# k1fm-pico-balloon-v1_1.net
KiCad netlist of a schematic drawn in EAGLE
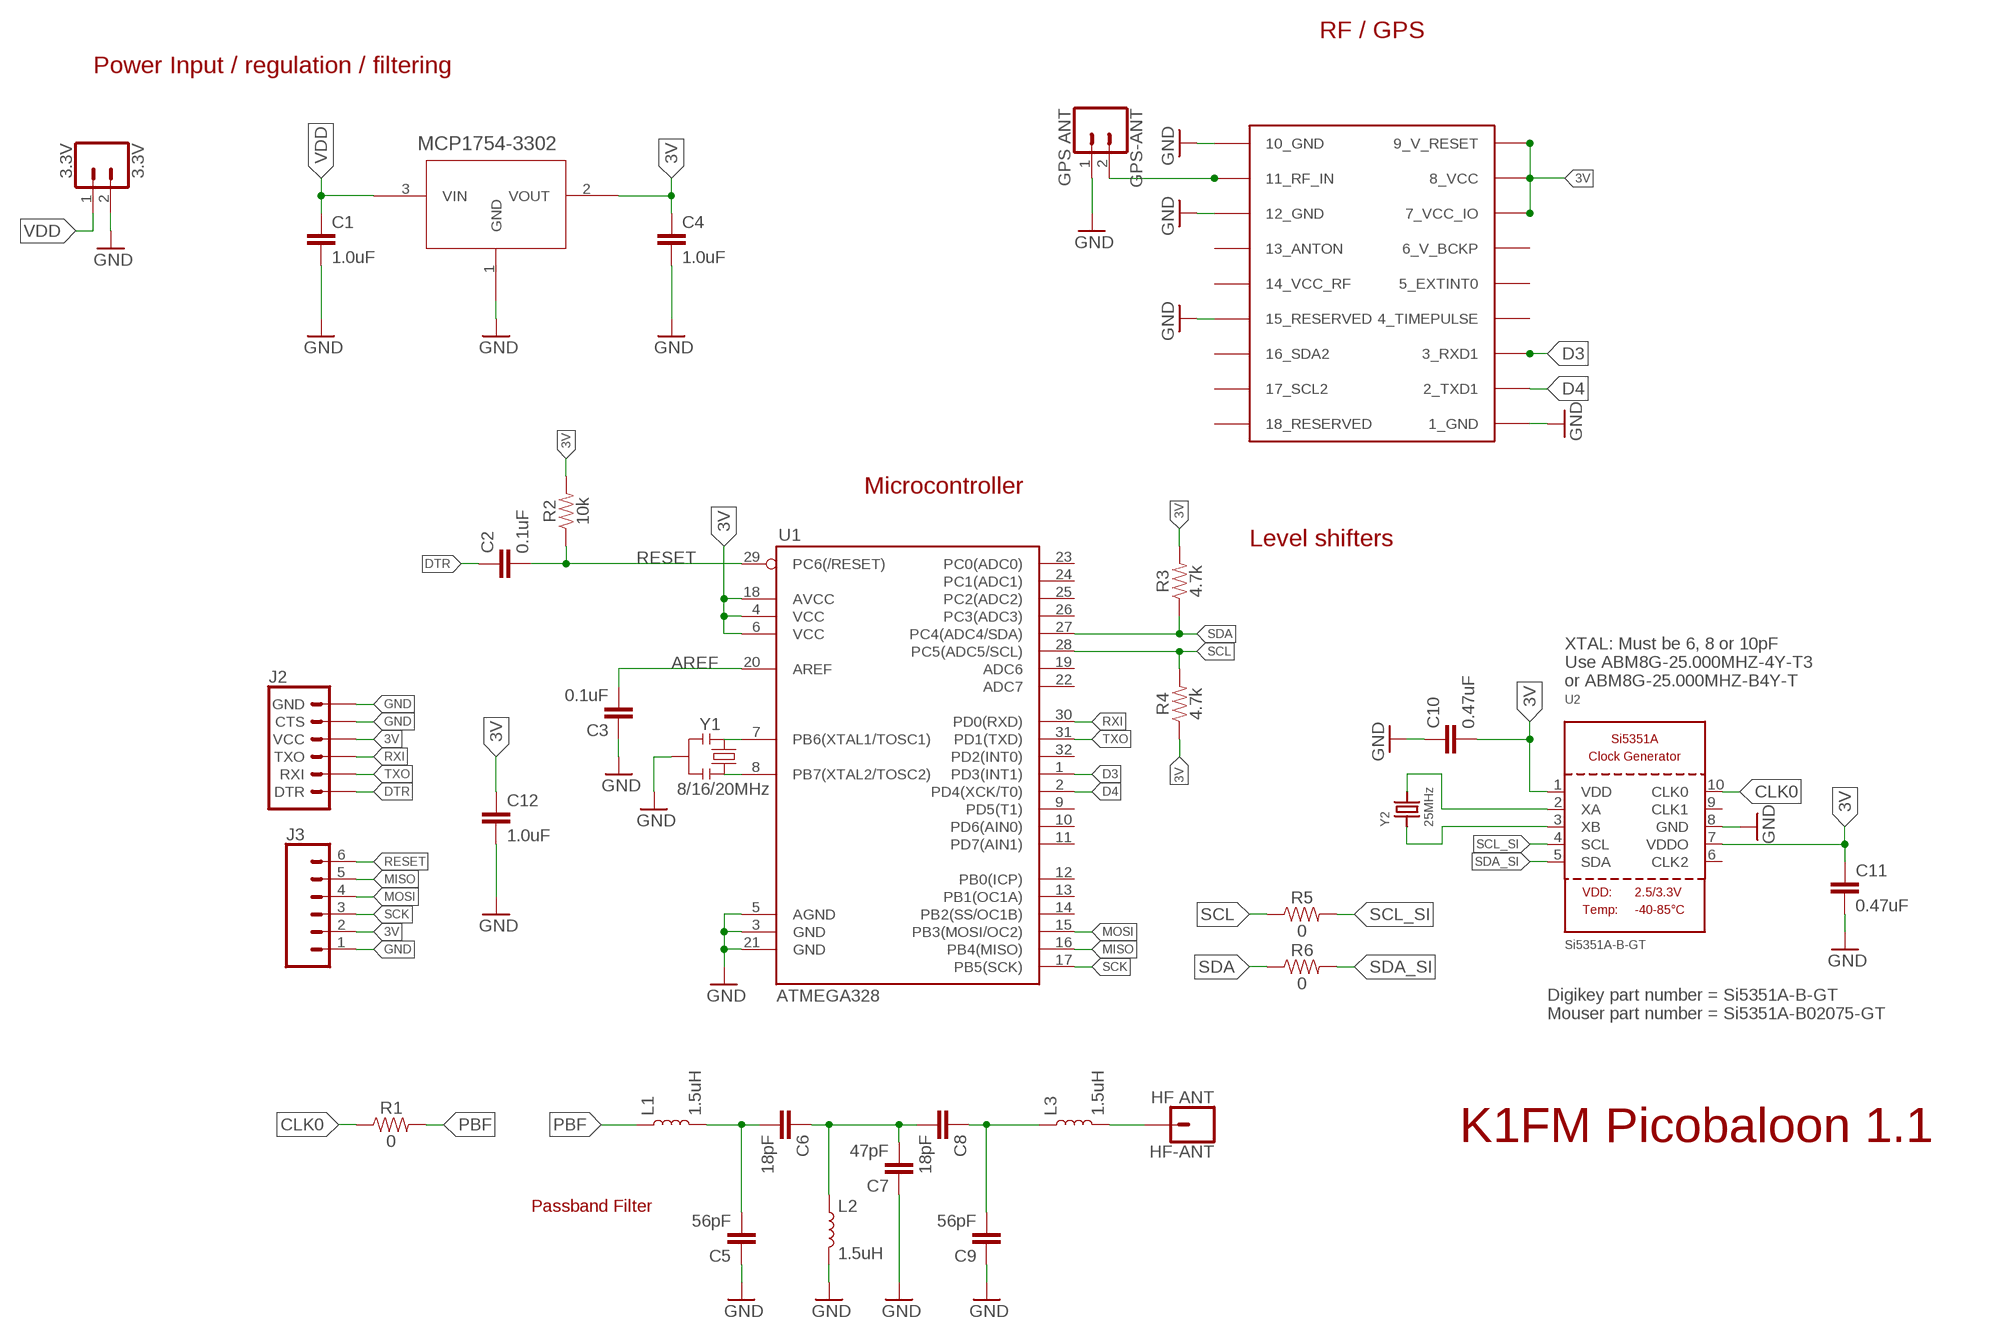
[diagram p0: schematic, sheet 1]

(export (version "E")
  (design (tool "Eeschema 10.0.6"))
  (components
    (comp (ref "3.3V")
      (value "3.3V")
      (footprint "eagle-import:1X02")
      (libsource (lib "eagle-import") (part "CONN_02"))
    )
    (comp (ref "C1")
      (value "1.0uF")
      (footprint "eagle-import:0603")
      (libsource (lib "eagle-import") (part "1.0UF-0603-16V-10%"))
    )
    (comp (ref "C2")
      (value "0.1uF")
      (footprint "eagle-import:0603")
      (libsource (lib "eagle-import") (part "0.1UF-0603-25V-5%"))
    )
    (comp (ref "C3")
      (value "0.1uF")
      (footprint "eagle-import:0603")
      (libsource (lib "eagle-import") (part "0.1UF-0603-25V-5%"))
    )
    (comp (ref "C4")
      (value "1.0uF")
      (footprint "eagle-import:0603")
      (libsource (lib "eagle-import") (part "1.0UF-0603-16V-10%"))
    )
    (comp (ref "C5")
      (value "56pF")
      (footprint "eagle-import:0603")
      (libsource (lib "eagle-import") (part "0.1UF-0603-25V-5%"))
    )
    (comp (ref "C6")
      (value "18pF")
      (footprint "eagle-import:0603")
      (libsource (lib "eagle-import") (part "0.1UF-0603-25V-5%"))
    )
    (comp (ref "C7")
      (value "47pF")
      (footprint "eagle-import:0603")
      (libsource (lib "eagle-import") (part "0.1UF-0603-25V-5%"))
    )
    (comp (ref "C8")
      (value "18pF")
      (footprint "eagle-import:0603")
      (libsource (lib "eagle-import") (part "0.1UF-0603-25V-5%"))
    )
    (comp (ref "C9")
      (value "56pF")
      (footprint "eagle-import:0603")
      (libsource (lib "eagle-import") (part "0.1UF-0603-25V-5%"))
    )
    (comp (ref "C10")
      (value "0.47uF")
      (footprint "eagle-import:0603")
      (libsource (lib "eagle-import") (part "0.1UF-0603-25V-5%"))
    )
    (comp (ref "C11")
      (value "0.47uF")
      (footprint "eagle-import:0603")
      (libsource (lib "eagle-import") (part "0.1UF-0603-25V-5%"))
    )
    (comp (ref "C12")
      (value "1.0uF")
      (footprint "eagle-import:0603")
      (libsource (lib "eagle-import") (part "1.0UF-0603-16V-10%"))
    )
    (comp (ref "GPS-ANT")
      (value "GPS ANT")
      (footprint "eagle-import:1X02")
      (libsource (lib "eagle-import") (part "CONN_02"))
    )
    (comp (ref "GPS1")
      (value "UBLOX_MAX")
      (footprint "eagle-import:UBLOX_MAX")
      (libsource (lib "eagle-import") (part "UBLOX_MAX"))
    )
    (comp (ref "HF-ANT")
      (value "HF ANT")
      (footprint "eagle-import:1X01")
      (libsource (lib "eagle-import") (part "CONN_01"))
    )
    (comp (ref "J2")
      (value "6_PIN_SERIAL_TARGET")
      (footprint "eagle-import:1X06")
      (libsource (lib "eagle-import") (part "6_PIN_SERIAL_TARGET"))
    )
    (comp (ref "J3")
      (value "CONN_06SILK_FEMALE_PTH")
      (footprint "eagle-import:1X06")
      (libsource (lib "eagle-import") (part "CONN_06SILK_FEMALE_PTH"))
    )
    (comp (ref "L1")
      (value "1.5uH")
      (footprint "eagle-import:0603")
      (libsource (lib "eagle-import") (part "INDUCTOR-0603-33NH"))
    )
    (comp (ref "L2")
      (value "1.5uH")
      (footprint "eagle-import:0603")
      (libsource (lib "eagle-import") (part "INDUCTOR-0603-33NH"))
    )
    (comp (ref "L3")
      (value "1.5uH")
      (footprint "eagle-import:0603")
      (libsource (lib "eagle-import") (part "INDUCTOR-0603-33NH"))
    )
    (comp (ref "R1")
      (value "0")
      (footprint "eagle-import:0603")
      (libsource (lib "eagle-import") (part "0OHM-0603-1/10W-5%"))
    )
    (comp (ref "R2")
      (value "10k")
      (footprint "eagle-import:0603")
      (libsource (lib "eagle-import") (part "10KOHM-0603-1/10W-1%"))
    )
    (comp (ref "R3")
      (value "4.7k")
      (footprint "eagle-import:0603")
      (libsource (lib "eagle-import") (part "4.7KOHM-0603-1/10W-1%"))
    )
    (comp (ref "R4")
      (value "4.7k")
      (footprint "eagle-import:0603")
      (libsource (lib "eagle-import") (part "4.7KOHM-0603-1/10W-1%"))
    )
    (comp (ref "R5")
      (value "0")
      (footprint "eagle-import:0603")
      (libsource (lib "eagle-import") (part "0OHM-0603-1/10W-5%"))
    )
    (comp (ref "R6")
      (value "0")
      (footprint "eagle-import:0603")
      (libsource (lib "eagle-import") (part "0OHM-0603-1/10W-5%"))
    )
    (comp (ref "U1")
      (value "ATMEGA328")
      (footprint "eagle-import:TQFP32-08")
      (libsource (lib "eagle-import") (part "ATMEGA168"))
    )
    (comp (ref "U2")
      (value "Si5351A-B-GT")
      (footprint "eagle-import:MSOP10")
      (libsource (lib "eagle-import") (part "SI5351A"))
    )
    (comp (ref "U3")
      (value "MCP1754X-XXXXX/C")
      (footprint "eagle-import:SOT-23A_MC")
      (libsource (lib "eagle-import") (part "MCP1754X-XXXXX/C"))
    )
    (comp (ref "Y1")
      (value "8/16/20MHz")
      (footprint "eagle-import:RESONATOR-SMD-1_1")
      (libsource (lib "eagle-import") (part "RESONATOR1{colon}1"))
    )
    (comp (ref "Y2")
      (value "25MHz")
      (footprint "eagle-import:CRYSTAL_3.2X2.5")
      (libsource (lib "eagle-import") (part "CRYSTAL3.2X2.5"))
    )
  )
  (nets
    (net (code "1") (name "/AREF") (class "Default")
      (node (ref "C3") (pin "2") (pinfunction "2_2") (pintype "passive"))
      (node (ref "U1") (pin "20") (pinfunction "AREF_20") (pintype "bidirectional"))
    )
    (net (code "2") (name "3V") (class "Default")
      (node (ref "C10") (pin "2") (pinfunction "2_2") (pintype "passive"))
      (node (ref "C11") (pin "1") (pinfunction "1_1") (pintype "passive"))
      (node (ref "C12") (pin "1") (pinfunction "1_1") (pintype "passive"))
      (node (ref "C4") (pin "1") (pinfunction "1_1") (pintype "passive"))
      (node (ref "GPS1") (pin "7_VCC_IO") (pinfunction "7_VCC_IO_7_VCC_IO") (pintype "power_in"))
      (node (ref "GPS1") (pin "8_VCC") (pinfunction "8_VCC_8_VCC") (pintype "power_in"))
      (node (ref "GPS1") (pin "9_V_RESET") (pinfunction "9_V_RESET_9_V_RESET") (pintype "power_in"))
      (node (ref "J2") (pin "4") (pinfunction "VCC_4") (pintype "passive"))
      (node (ref "J3") (pin "2") (pinfunction "2_2") (pintype "passive"))
      (node (ref "R2") (pin "2") (pinfunction "2_2") (pintype "passive"))
      (node (ref "R3") (pin "2") (pinfunction "2_2") (pintype "passive"))
      (node (ref "R4") (pin "1") (pinfunction "1_1") (pintype "passive"))
      (node (ref "U1") (pin "18") (pinfunction "AVCC_18") (pintype "bidirectional"))
      (node (ref "U1") (pin "4") (pinfunction "VCC_4") (pintype "bidirectional"))
      (node (ref "U1") (pin "6") (pinfunction "VCC_6") (pintype "bidirectional"))
      (node (ref "U2") (pin "1") (pinfunction "VDD_1") (pintype "power_in"))
      (node (ref "U2") (pin "7") (pinfunction "VDDO_7") (pintype "power_in"))
      (node (ref "U3") (pin "2") (pinfunction "VOUT_2") (pintype "passive"))
    )
    (net (code "3") (name "CLK0") (class "Default")
      (node (ref "R1") (pin "1") (pinfunction "1_1") (pintype "passive"))
      (node (ref "U2") (pin "10") (pinfunction "CLK0_10") (pintype "output"))
    )
    (net (code "4") (name "D3") (class "Default")
      (node (ref "GPS1") (pin "3_RXD1") (pinfunction "3_RXD1_3_RXD1") (pintype "bidirectional"))
      (node (ref "U1") (pin "1") (pinfunction "PD3(INT1)_1") (pintype "bidirectional"))
    )
    (net (code "5") (name "D4") (class "Default")
      (node (ref "GPS1") (pin "2_TXD1") (pinfunction "2_TXD1_2_TXD1") (pintype "bidirectional"))
      (node (ref "U1") (pin "2") (pinfunction "PD4(XCK/T0)_2") (pintype "bidirectional"))
    )
    (net (code "6") (name "DTR") (class "Default")
      (node (ref "C2") (pin "1") (pinfunction "1_1") (pintype "passive"))
      (node (ref "J2") (pin "1") (pinfunction "DTR_1") (pintype "passive"))
    )
    (net (code "7") (name "GND") (class "Default")
      (node (ref "3.3V") (pin "2") (pinfunction "2_2") (pintype "passive"))
      (node (ref "C1") (pin "2") (pinfunction "2_2") (pintype "passive"))
      (node (ref "C10") (pin "1") (pinfunction "1_1") (pintype "passive"))
      (node (ref "C11") (pin "2") (pinfunction "2_2") (pintype "passive"))
      (node (ref "C12") (pin "2") (pinfunction "2_2") (pintype "passive"))
      (node (ref "C3") (pin "1") (pinfunction "1_1") (pintype "passive"))
      (node (ref "C4") (pin "2") (pinfunction "2_2") (pintype "passive"))
      (node (ref "C5") (pin "1") (pinfunction "1_1") (pintype "passive"))
      (node (ref "C7") (pin "1") (pinfunction "1_1") (pintype "passive"))
      (node (ref "C9") (pin "1") (pinfunction "1_1") (pintype "passive"))
      (node (ref "GPS-ANT") (pin "1") (pinfunction "1_1") (pintype "passive"))
      (node (ref "GPS1") (pin "10_GND") (pinfunction "10_GND_10_GND") (pintype "power_in"))
      (node (ref "GPS1") (pin "12_GND") (pinfunction "12_GND_12_GND") (pintype "power_in"))
      (node (ref "GPS1") (pin "15_RESERVED") (pinfunction "15_RESERVED_15_RESERVED") (pintype "bidirectional"))
      (node (ref "GPS1") (pin "1_GND") (pinfunction "1_GND_1_GND") (pintype "power_in"))
      (node (ref "J2") (pin "5") (pinfunction "CTS_5") (pintype "passive"))
      (node (ref "J2") (pin "6") (pinfunction "GND_6") (pintype "passive"))
      (node (ref "J3") (pin "1") (pinfunction "1_1") (pintype "passive"))
      (node (ref "L2") (pin "2") (pinfunction "2_2") (pintype "passive"))
      (node (ref "U1") (pin "21") (pinfunction "GND_21") (pintype "bidirectional"))
      (node (ref "U1") (pin "3") (pinfunction "GND_3") (pintype "bidirectional"))
      (node (ref "U1") (pin "5") (pinfunction "AGND_5") (pintype "bidirectional"))
      (node (ref "U2") (pin "8") (pinfunction "GND_8") (pintype "power_in"))
      (node (ref "U3") (pin "1") (pinfunction "GND_1") (pintype "passive"))
      (node (ref "Y1") (pin "2") (pinfunction "2_2") (pintype "passive"))
    )
    (net (code "8") (name "MISO") (class "Default")
      (node (ref "J3") (pin "5") (pinfunction "5_5") (pintype "passive"))
      (node (ref "U1") (pin "16") (pinfunction "PB4(MISO)_16") (pintype "bidirectional"))
    )
    (net (code "9") (name "MOSI") (class "Default")
      (node (ref "J3") (pin "4") (pinfunction "4_4") (pintype "passive"))
      (node (ref "U1") (pin "15") (pinfunction "PB3(MOSI/OC2)_15") (pintype "bidirectional"))
    )
    (net (code "10") (name "Net-(C5-Pad2)") (class "Default")
      (node (ref "C5") (pin "2") (pinfunction "2_2") (pintype "passive"))
      (node (ref "C6") (pin "2") (pinfunction "2_2") (pintype "passive"))
      (node (ref "L1") (pin "2") (pinfunction "2_2") (pintype "passive"))
    )
    (net (code "11") (name "Net-(C6-Pad1)") (class "Default")
      (node (ref "C6") (pin "1") (pinfunction "1_1") (pintype "passive"))
      (node (ref "C7") (pin "2") (pinfunction "2_2") (pintype "passive"))
      (node (ref "C8") (pin "2") (pinfunction "2_2") (pintype "passive"))
      (node (ref "L2") (pin "1") (pinfunction "1_1") (pintype "passive"))
    )
    (net (code "12") (name "Net-(C8-Pad1)") (class "Default")
      (node (ref "C8") (pin "1") (pinfunction "1_1") (pintype "passive"))
      (node (ref "C9") (pin "2") (pinfunction "2_2") (pintype "passive"))
      (node (ref "L3") (pin "1") (pinfunction "1_1") (pintype "passive"))
    )
    (net (code "13") (name "Net-(GPS-ANT-Pad2)") (class "Default")
      (node (ref "GPS-ANT") (pin "2") (pinfunction "2_2") (pintype "passive"))
      (node (ref "GPS1") (pin "11_RF_IN") (pinfunction "11_RF_IN_11_RF_IN") (pintype "bidirectional"))
    )
    (net (code "14") (name "Net-(HF-ANT-Pad1)") (class "Default")
      (node (ref "HF-ANT") (pin "1") (pinfunction "1_1") (pintype "passive"))
      (node (ref "L3") (pin "2") (pinfunction "2_2") (pintype "passive"))
    )
    (net (code "15") (name "Net-(U1-PB6(XTAL1{slash}TOSC1))") (class "Default")
      (node (ref "U1") (pin "7") (pinfunction "PB6(XTAL1/TOSC1)_7") (pintype "bidirectional"))
      (node (ref "Y1") (pin "1") (pinfunction "1_1") (pintype "passive"))
    )
    (net (code "16") (name "Net-(U1-PB7(XTAL2{slash}TOSC2))") (class "Default")
      (node (ref "U1") (pin "8") (pinfunction "PB7(XTAL2/TOSC2)_8") (pintype "bidirectional"))
      (node (ref "Y1") (pin "3") (pinfunction "3_3") (pintype "passive"))
    )
    (net (code "17") (name "Net-(U2-XA)") (class "Default")
      (node (ref "U2") (pin "2") (pinfunction "XA_2") (pintype "input"))
      (node (ref "Y2") (pin "2") (pinfunction "2_2") (pintype "passive"))
    )
    (net (code "18") (name "Net-(U2-XB)") (class "Default")
      (node (ref "U2") (pin "3") (pinfunction "XB_3") (pintype "input"))
      (node (ref "Y2") (pin "1") (pinfunction "1_1") (pintype "passive"))
    )
    (net (code "19") (name "PBF") (class "Default")
      (node (ref "L1") (pin "1") (pinfunction "1_1") (pintype "passive"))
      (node (ref "R1") (pin "2") (pinfunction "2_2") (pintype "passive"))
    )
    (net (code "20") (name "RESET") (class "Default")
      (node (ref "C2") (pin "2") (pinfunction "2_2") (pintype "passive"))
      (node (ref "J3") (pin "6") (pinfunction "6_6") (pintype "passive"))
      (node (ref "R2") (pin "1") (pinfunction "1_1") (pintype "passive"))
      (node (ref "U1") (pin "29") (pinfunction "PC6(/RESET)_29") (pintype "bidirectional"))
    )
    (net (code "21") (name "RXI") (class "Default")
      (node (ref "J2") (pin "3") (pinfunction "TXO_3") (pintype "passive"))
      (node (ref "U1") (pin "30") (pinfunction "PD0(RXD)_30") (pintype "bidirectional"))
    )
    (net (code "22") (name "SCK") (class "Default")
      (node (ref "J3") (pin "3") (pinfunction "3_3") (pintype "passive"))
      (node (ref "U1") (pin "17") (pinfunction "PB5(SCK)_17") (pintype "bidirectional"))
    )
    (net (code "23") (name "SCL") (class "Default")
      (node (ref "R4") (pin "2") (pinfunction "2_2") (pintype "passive"))
      (node (ref "R5") (pin "1") (pinfunction "1_1") (pintype "passive"))
      (node (ref "U1") (pin "28") (pinfunction "PC5(ADC5/SCL)_28") (pintype "bidirectional"))
    )
    (net (code "24") (name "SCL_SI") (class "Default")
      (node (ref "R5") (pin "2") (pinfunction "2_2") (pintype "passive"))
      (node (ref "U2") (pin "4") (pinfunction "SCL_4") (pintype "input"))
    )
    (net (code "25") (name "SDA") (class "Default")
      (node (ref "R3") (pin "1") (pinfunction "1_1") (pintype "passive"))
      (node (ref "R6") (pin "1") (pinfunction "1_1") (pintype "passive"))
      (node (ref "U1") (pin "27") (pinfunction "PC4(ADC4/SDA)_27") (pintype "bidirectional"))
    )
    (net (code "26") (name "SDA_SI") (class "Default")
      (node (ref "R6") (pin "2") (pinfunction "2_2") (pintype "passive"))
      (node (ref "U2") (pin "5") (pinfunction "SDA_5") (pintype "bidirectional"))
    )
    (net (code "27") (name "TXO") (class "Default")
      (node (ref "J2") (pin "2") (pinfunction "RXI_2") (pintype "passive"))
      (node (ref "U1") (pin "31") (pinfunction "PD1(TXD)_31") (pintype "bidirectional"))
    )
    (net (code "28") (name "VDD") (class "Default")
      (node (ref "3.3V") (pin "1") (pinfunction "1_1") (pintype "passive"))
      (node (ref "C1") (pin "1") (pinfunction "1_1") (pintype "passive"))
      (node (ref "U3") (pin "3") (pinfunction "VIN_3") (pintype "passive"))
    )
    (net (code "29") (name "unconnected-(GPS1-Pad4_TIMEPULSE)") (class "Default")
      (node (ref "GPS1") (pin "4_TIMEPULSE") (pinfunction "4_TIMEPULSE_4_TIMEPULSE") (pintype "bidirectional"))
    )
    (net (code "30") (name "unconnected-(GPS1-Pad5_EXTINT0)") (class "Default")
      (node (ref "GPS1") (pin "5_EXTINT0") (pinfunction "5_EXTINT0_5_EXTINT0") (pintype "bidirectional"))
    )
    (net (code "31") (name "unconnected-(GPS1-Pad6_V_BCKP)") (class "Default")
      (node (ref "GPS1") (pin "6_V_BCKP") (pinfunction "6_V_BCKP_6_V_BCKP") (pintype "bidirectional"))
    )
    (net (code "32") (name "unconnected-(GPS1-Pad13_ANTON)") (class "Default")
      (node (ref "GPS1") (pin "13_ANTON") (pinfunction "13_ANTON_13_ANTON") (pintype "bidirectional"))
    )
    (net (code "33") (name "unconnected-(GPS1-Pad14_VCC_RF)") (class "Default")
      (node (ref "GPS1") (pin "14_VCC_RF") (pinfunction "14_VCC_RF_14_VCC_RF") (pintype "bidirectional"))
    )
    (net (code "34") (name "unconnected-(GPS1-Pad16_SDA2)") (class "Default")
      (node (ref "GPS1") (pin "16_SDA2") (pinfunction "16_SDA2_16_SDA2") (pintype "bidirectional"))
    )
    (net (code "35") (name "unconnected-(GPS1-Pad17_SCL2)") (class "Default")
      (node (ref "GPS1") (pin "17_SCL2") (pinfunction "17_SCL2_17_SCL2") (pintype "bidirectional"))
    )
    (net (code "36") (name "unconnected-(GPS1-Pad18_RESERVED)") (class "Default")
      (node (ref "GPS1") (pin "18_RESERVED") (pinfunction "18_RESERVED_18_RESERVED") (pintype "bidirectional"))
    )
    (net (code "37") (name "unconnected-(U1-ADC6-Pad19)") (class "Default")
      (node (ref "U1") (pin "19") (pinfunction "ADC6_19") (pintype "bidirectional"))
    )
    (net (code "38") (name "unconnected-(U1-ADC7-Pad22)") (class "Default")
      (node (ref "U1") (pin "22") (pinfunction "ADC7_22") (pintype "bidirectional"))
    )
    (net (code "39") (name "unconnected-(U1-PB0(ICP)-Pad12)") (class "Default")
      (node (ref "U1") (pin "12") (pinfunction "PB0(ICP)_12") (pintype "bidirectional"))
    )
    (net (code "40") (name "unconnected-(U1-PB1(OC1A)-Pad13)") (class "Default")
      (node (ref "U1") (pin "13") (pinfunction "PB1(OC1A)_13") (pintype "bidirectional"))
    )
    (net (code "41") (name "unconnected-(U1-PB2(SS{slash}OC1B)-Pad14)") (class "Default")
      (node (ref "U1") (pin "14") (pinfunction "PB2(SS/OC1B)_14") (pintype "bidirectional"))
    )
    (net (code "42") (name "unconnected-(U1-PC0(ADC0)-Pad23)") (class "Default")
      (node (ref "U1") (pin "23") (pinfunction "PC0(ADC0)_23") (pintype "bidirectional"))
    )
    (net (code "43") (name "unconnected-(U1-PC1(ADC1)-Pad24)") (class "Default")
      (node (ref "U1") (pin "24") (pinfunction "PC1(ADC1)_24") (pintype "bidirectional"))
    )
    (net (code "44") (name "unconnected-(U1-PC2(ADC2)-Pad25)") (class "Default")
      (node (ref "U1") (pin "25") (pinfunction "PC2(ADC2)_25") (pintype "bidirectional"))
    )
    (net (code "45") (name "unconnected-(U1-PC3(ADC3)-Pad26)") (class "Default")
      (node (ref "U1") (pin "26") (pinfunction "PC3(ADC3)_26") (pintype "bidirectional"))
    )
    (net (code "46") (name "unconnected-(U1-PD2(INT0)-Pad32)") (class "Default")
      (node (ref "U1") (pin "32") (pinfunction "PD2(INT0)_32") (pintype "bidirectional"))
    )
    (net (code "47") (name "unconnected-(U1-PD5(T1)-Pad9)") (class "Default")
      (node (ref "U1") (pin "9") (pinfunction "PD5(T1)_9") (pintype "bidirectional"))
    )
    (net (code "48") (name "unconnected-(U1-PD6(AIN0)-Pad10)") (class "Default")
      (node (ref "U1") (pin "10") (pinfunction "PD6(AIN0)_10") (pintype "bidirectional"))
    )
    (net (code "49") (name "unconnected-(U1-PD7(AIN1)-Pad11)") (class "Default")
      (node (ref "U1") (pin "11") (pinfunction "PD7(AIN1)_11") (pintype "bidirectional"))
    )
    (net (code "50") (name "unconnected-(U2-CLK1-Pad9)") (class "Default")
      (node (ref "U2") (pin "9") (pinfunction "CLK1_9") (pintype "output"))
    )
    (net (code "51") (name "unconnected-(U2-CLK2-Pad6)") (class "Default")
      (node (ref "U2") (pin "6") (pinfunction "CLK2_6") (pintype "output"))
    )
  )
)
